# STM32MP25XXAK_I_Os.net
KiCad netlist of a schematic drawn in Altium Designer
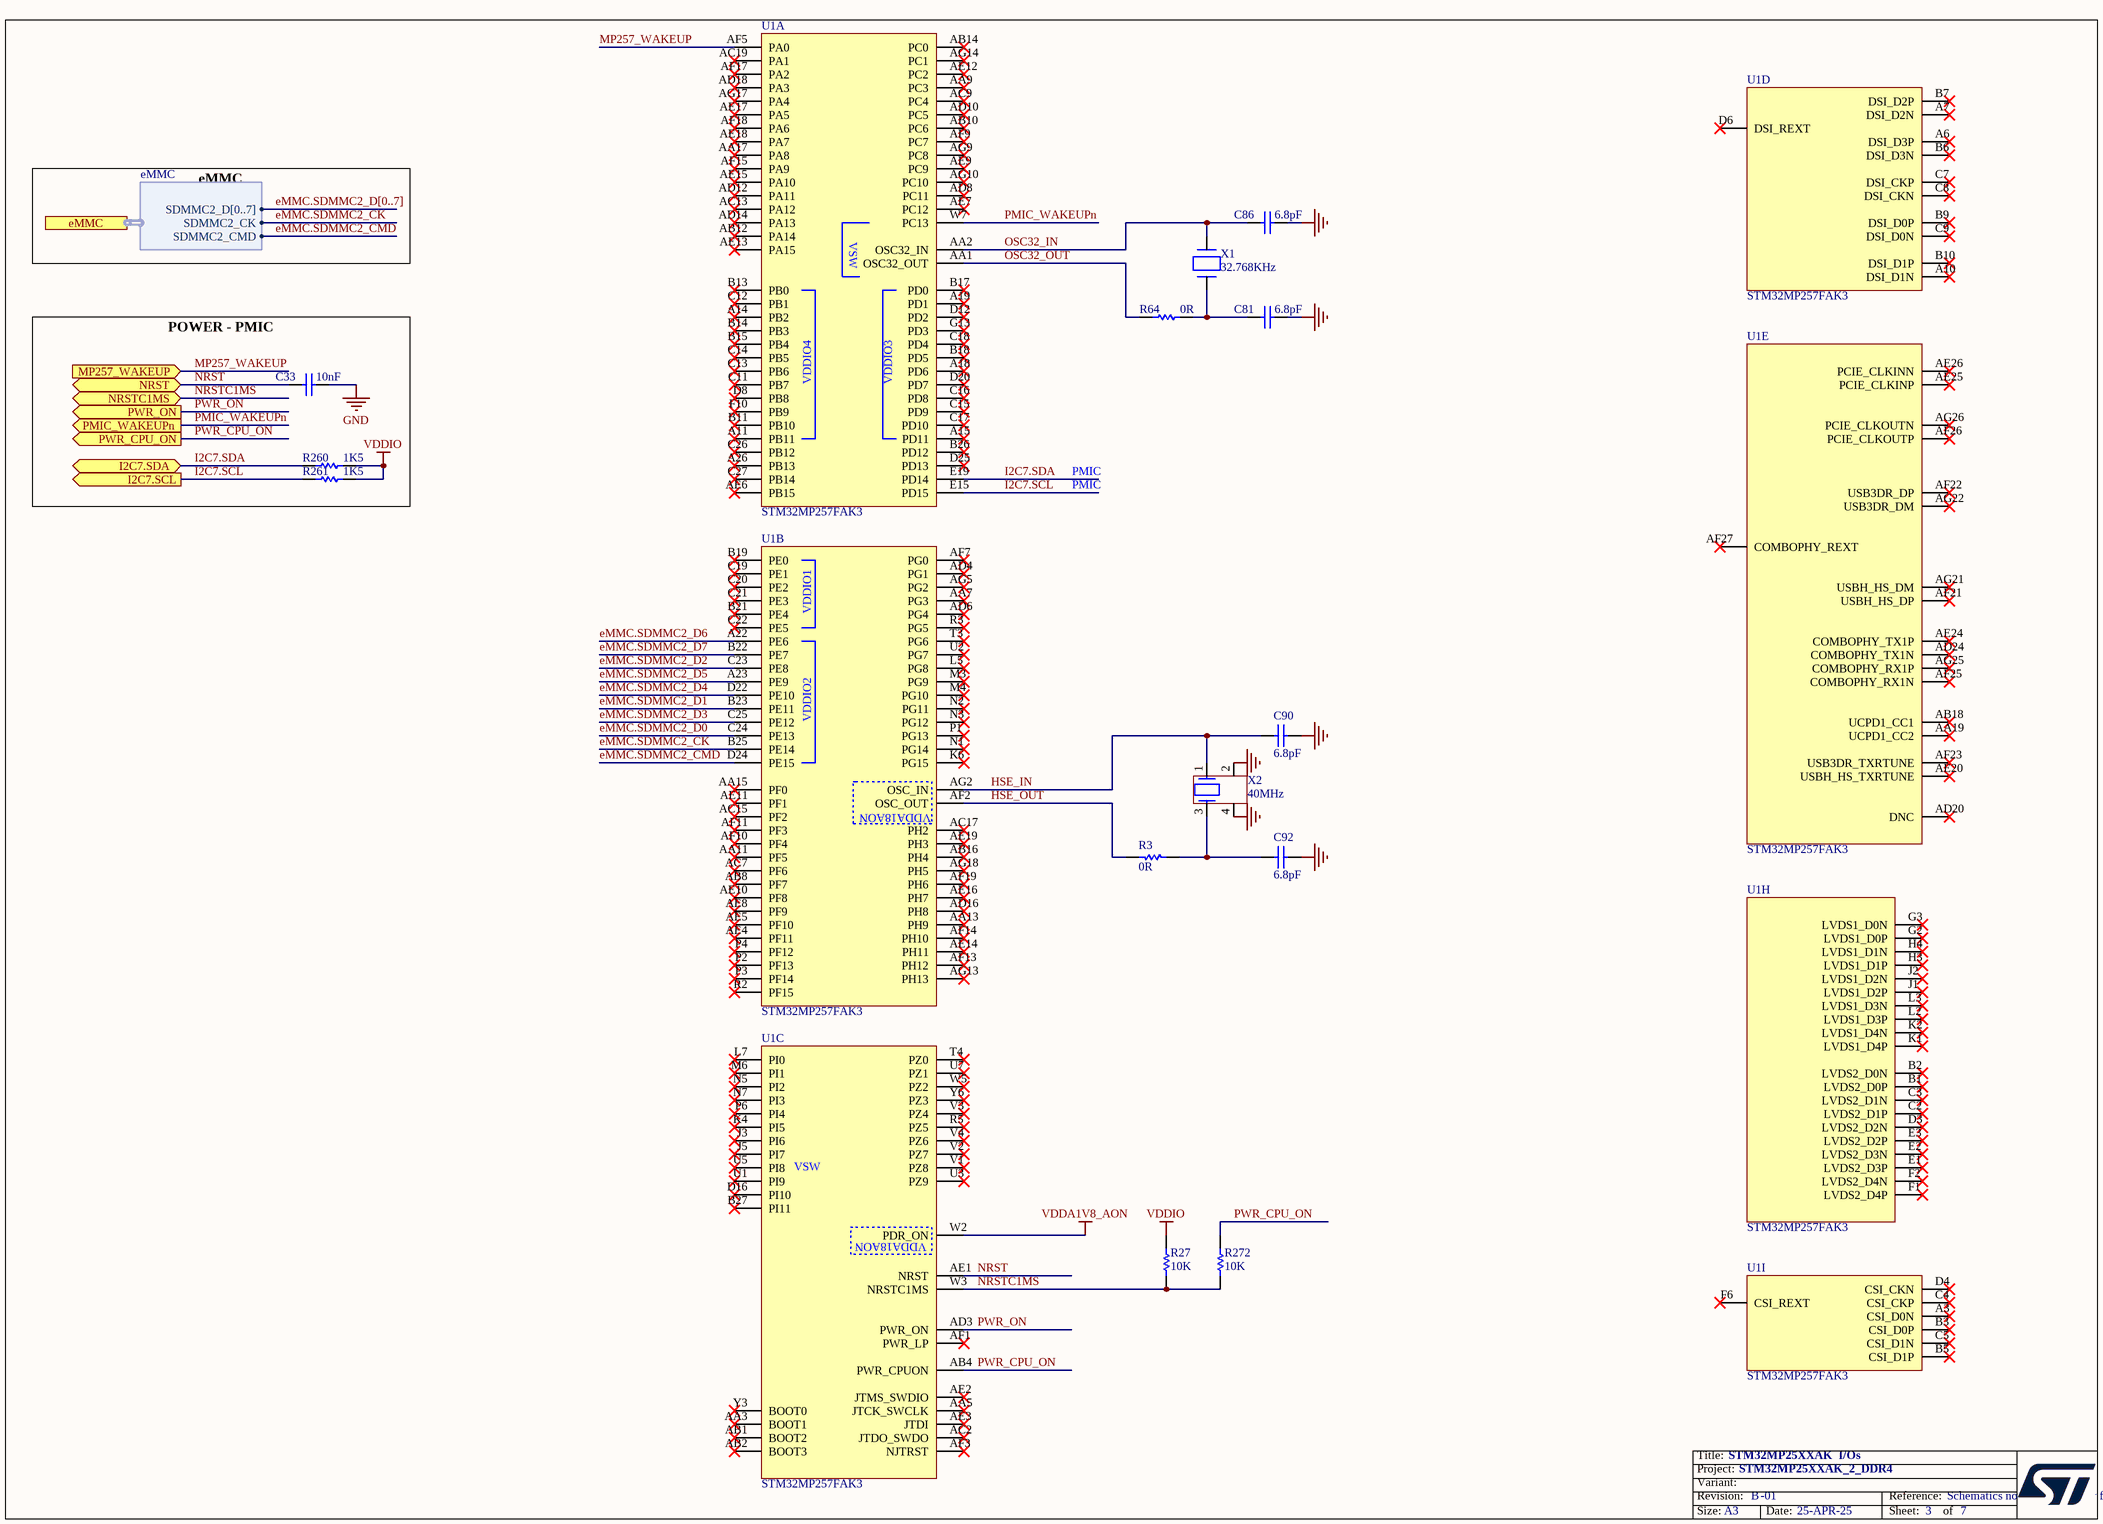
[diagram p0: STM32MP25XXAK I_Os.SchDoc]

(export (version "E")
  (design (tool "Eeschema 10.0.6"))
  (components
    (comp (ref "C33")
      (value "10nF")
      (footprint "C0402")
      (description "Capacitor, MLCC, 10nF, 16V, X7R, 10%, 0402, T=0.5mm")
      (fields
        (field (name "INTERNAL_PART_NUMBER") "MCD-00011")
        (field (name "MANUFACTURER_PART_NUMBER") "CC0402KRX7R7BB103")
        (field (name "PROVIDED_BY") "SUBCO")
      )
      (libsource (lib "MCD_PARTS_database") (part "Capacitor"))
    )
    (comp (ref "C81")
      (value "6.8pF")
      (footprint "C0402")
      (description "Capacitor, MLCC, 6.8pF, 50V, NPO, +-0.25pF, 0402, T=0.5mm")
      (fields
        (field (name "INTERNAL_PART_NUMBER") "MCD-00674")
        (field (name "MANUFACTURER_PART_NUMBER") "CC0402CRNPO9BN6R8")
        (field (name "PROVIDED_BY") "SUBCO")
      )
      (libsource (lib "MCD_PARTS_database") (part "Capacitor"))
    )
    (comp (ref "C86")
      (value "6.8pF")
      (footprint "C0402")
      (description "Capacitor, MLCC, 6.8pF, 50V, NPO, +-0.25pF, 0402, T=0.5mm")
      (fields
        (field (name "INTERNAL_PART_NUMBER") "MCD-00674")
        (field (name "MANUFACTURER_PART_NUMBER") "CC0402CRNPO9BN6R8")
        (field (name "PROVIDED_BY") "SUBCO")
      )
      (libsource (lib "MCD_PARTS_database") (part "Capacitor"))
    )
    (comp (ref "C90")
      (value "6.8pF")
      (footprint "C0402")
      (description "Capacitor, MLCC, 6.8pF, 50V, NPO, +-0.25pF, 0402, T=0.5mm")
      (fields
        (field (name "INTERNAL_PART_NUMBER") "MCD-00674")
        (field (name "MANUFACTURER_PART_NUMBER") "CC0402CRNPO9BN6R8")
        (field (name "PROVIDED_BY") "SUBCO")
      )
      (libsource (lib "MCD_PARTS_database") (part "Capacitor"))
    )
    (comp (ref "C92")
      (value "6.8pF")
      (footprint "C0402")
      (description "Capacitor, MLCC, 6.8pF, 50V, NPO, +-0.25pF, 0402, T=0.5mm")
      (fields
        (field (name "INTERNAL_PART_NUMBER") "MCD-00674")
        (field (name "MANUFACTURER_PART_NUMBER") "CC0402CRNPO9BN6R8")
        (field (name "PROVIDED_BY") "SUBCO")
      )
      (libsource (lib "MCD_PARTS_database") (part "Capacitor"))
    )
    (comp (ref "R3")
      (value "0R")
      (footprint "R0402")
      (description "Resistor,0R,0402,5%,1/16W")
      (fields
        (field (name "INTERNAL_PART_NUMBER") "MCD-00052")
        (field (name "MANUFACTURER_PART_NUMBER") "RC0402JR-070RL")
        (field (name "PROVIDED_BY") "SUBCO")
      )
      (libsource (lib "MCD_PARTS_database") (part "Resistor"))
    )
    (comp (ref "R27")
      (value "10K")
      (footprint "R0402")
      (description "Resistor,10K,0402,1%,1/16W")
      (fields (field (name "INTERNAL_PART_NUMBER") "MCD-00053") (field (name "BMS_PART_NUMBER") "9131590"))
      (libsource (lib "MCD_PARTS_database") (part "Resistor"))
    )
    (comp (ref "R64")
      (value "0R")
      (footprint "R0402")
      (description "Resistor,0R,0402,5%,1/16W")
      (fields
        (field (name "INTERNAL_PART_NUMBER") "MCD-00052")
        (field (name "MANUFACTURER_PART_NUMBER") "RC0402JR-070RL")
        (field (name "PROVIDED_BY") "SUBCO")
      )
      (libsource (lib "MCD_PARTS_database") (part "Resistor"))
    )
    (comp (ref "R260")
      (value "1K5")
      (footprint "R0402")
      (description "Resistor,1K5,0402,1%,1/16W")
      (fields (field (name "INTERNAL_PART_NUMBER") "MCD-00068") (field (name "MANUFACTURER") "YAGEO"))
      (libsource (lib "MCD_PARTS_database") (part "Resistor"))
    )
    (comp (ref "R261")
      (value "1K5")
      (footprint "R0402")
      (description "Resistor,1K5,0402,1%,1/16W")
      (fields (field (name "INTERNAL_PART_NUMBER") "MCD-00068") (field (name "MANUFACTURER") "YAGEO"))
      (libsource (lib "MCD_PARTS_database") (part "Resistor"))
    )
    (comp (ref "R272")
      (value "10K")
      (footprint "R0402")
      (description "Resistor,10K,0402,1%,1/16W")
      (fields (field (name "INTERNAL_PART_NUMBER") "MCD-00053") (field (name "BMS_PART_NUMBER") "9131590"))
      (libsource (lib "MCD_PARTS_database") (part "Resistor"))
    )
    (comp (ref "U1")
      (value "STM32MP257FAK3")
      (footprint "ICC_TFBGA424_14X14_P050_H1P20_CODE-B0A2")
      (description "MPU , 2xCortex-A35@1.5GHz, Cortex-M33@400MHz, TFBGA 14x14, pitch 0.5, 648KB SRAM, With Crypto")
      (fields
        (field (name "INTERNAL_PART_NUMBER") "MCD-03375")
        (field (name "MANUFACTURER") "STMICROELECTRONICS")
      )
      (libsource (lib "MCD_PARTS_database") (part "STM32MP257FAK3"))
    )
    (comp (ref "X1")
      (value "32.768KHz")
      (footprint "CRY_NX2012SA_2P")
      (description "Crystal, 32.768kHz, 6pF, +/-20ppm, 80K, 2.05x1.2mm")
      (fields (field (name "INTERNAL_PART_NUMBER") "MCD-01479") (field (name "BMS_PART_NUMBER") "9157049"))
      (libsource (lib "MCD_PARTS_database") (part "XTAL_2_PINS"))
    )
    (comp (ref "X2")
      (value "40MHz")
      (footprint "CRY_NX1612SA_4P")
      (description "Crystal, 40MHz, 6pF, +/-20ppm, 80R, 1.6x1.2mm")
      (fields (field (name "INTERNAL_PART_NUMBER") "MCD-02344") (field (name "MANUFACTURER") "NDK"))
      (libsource (lib "MCD_PARTS_database") (part "XTAL_4_PINS"))
    )
  )
  (nets
    (net (code "2") (name "/HSE_IN") (class "Default")
      (node (ref "C90") (pin "2") (pinfunction "2_2") (pintype "passive"))
      (node (ref "U1") (pin "AG2") (pinfunction "OSC_IN_AG2") (pintype "passive"))
      (node (ref "X2") (pin "1") (pinfunction "1_1") (pintype "passive"))
    )
    (net (code "3") (name "/HSE_OUT") (class "Default")
      (node (ref "R3") (pin "2") (pinfunction "2_2") (pintype "passive"))
      (node (ref "U1") (pin "AF2") (pinfunction "OSC_OUT_AF2") (pintype "passive"))
    )
    (net (code "4") (name "/I2C7.SCL") (class "Default")
      (node (ref "R261") (pin "1") (pinfunction "1_1") (pintype "passive"))
      (node (ref "U1") (pin "E15") (pinfunction "PD15_E15") (pintype "passive"))
    )
    (net (code "5") (name "/I2C7.SDA") (class "Default")
      (node (ref "R260") (pin "1") (pinfunction "1_1") (pintype "passive"))
      (node (ref "U1") (pin "E19") (pinfunction "PD14_E19") (pintype "passive"))
    )
    (net (code "6") (name "/MP257_WAKEUP") (class "Default")
      (node (ref "U1") (pin "AF5") (pinfunction "PA0_AF5") (pintype "passive"))
    )
    (net (code "7") (name "/NRST") (class "Default")
      (node (ref "C33") (pin "2") (pinfunction "2_2") (pintype "passive"))
      (node (ref "U1") (pin "AE1") (pinfunction "NRST_AE1") (pintype "passive"))
    )
    (net (code "8") (name "/NRSTC1MS") (class "Default")
      (node (ref "R27") (pin "1") (pinfunction "1_1") (pintype "passive"))
      (node (ref "R272") (pin "1") (pinfunction "1_1") (pintype "passive"))
      (node (ref "U1") (pin "W3") (pinfunction "NRSTC1MS_W3") (pintype "passive"))
    )
    (net (code "9") (name "/OSC32_IN") (class "Default")
      (node (ref "C86") (pin "1") (pinfunction "1_1") (pintype "passive"))
      (node (ref "U1") (pin "AA2") (pinfunction "OSC32_IN_AA2") (pintype "passive"))
      (node (ref "X1") (pin "2") (pinfunction "X2_2") (pintype "passive"))
    )
    (net (code "10") (name "/OSC32_OUT") (class "Default")
      (node (ref "R64") (pin "1") (pinfunction "1_1") (pintype "passive"))
      (node (ref "U1") (pin "AA1") (pinfunction "OSC32_OUT_AA1") (pintype "passive"))
    )
    (net (code "11") (name "/PMIC_WAKEUPn") (class "Default")
      (node (ref "U1") (pin "W7") (pinfunction "PC13_W7") (pintype "passive"))
    )
    (net (code "12") (name "/PWR_CPU_ON") (class "Default")
      (node (ref "R272") (pin "2") (pinfunction "2_2") (pintype "passive"))
      (node (ref "U1") (pin "AB4") (pinfunction "PWR_CPUON_AB4") (pintype "passive"))
    )
    (net (code "13") (name "/PWR_ON") (class "Default")
      (node (ref "U1") (pin "AD3") (pinfunction "PWR_ON_AD3") (pintype "passive"))
    )
    (net (code "14") (name "/eMMC.SDMMC2_CK") (class "Default")
      (node (ref "U1") (pin "B25") (pinfunction "PE14_B25") (pintype "passive"))
    )
    (net (code "15") (name "/eMMC.SDMMC2_CMD") (class "Default")
      (node (ref "U1") (pin "D24") (pinfunction "PE15_D24") (pintype "passive"))
    )
    (net (code "16") (name "/eMMC.SDMMC2_D0") (class "Default")
      (node (ref "U1") (pin "C24") (pinfunction "PE13_C24") (pintype "passive"))
    )
    (net (code "17") (name "/eMMC.SDMMC2_D1") (class "Default")
      (node (ref "U1") (pin "B23") (pinfunction "PE11_B23") (pintype "passive"))
    )
    (net (code "18") (name "/eMMC.SDMMC2_D2") (class "Default")
      (node (ref "U1") (pin "C23") (pinfunction "PE8_C23") (pintype "passive"))
    )
    (net (code "19") (name "/eMMC.SDMMC2_D3") (class "Default")
      (node (ref "U1") (pin "C25") (pinfunction "PE12_C25") (pintype "passive"))
    )
    (net (code "20") (name "/eMMC.SDMMC2_D4") (class "Default")
      (node (ref "U1") (pin "D22") (pinfunction "PE10_D22") (pintype "passive"))
    )
    (net (code "21") (name "/eMMC.SDMMC2_D5") (class "Default")
      (node (ref "U1") (pin "A23") (pinfunction "PE9_A23") (pintype "passive"))
    )
    (net (code "22") (name "/eMMC.SDMMC2_D6") (class "Default")
      (node (ref "U1") (pin "A22") (pinfunction "PE6_A22") (pintype "passive"))
    )
    (net (code "23") (name "/eMMC.SDMMC2_D7") (class "Default")
      (node (ref "U1") (pin "B22") (pinfunction "PE7_B22") (pintype "passive"))
    )
    (net (code "26") (name "GND") (class "Default")
      (node (ref "C33") (pin "1") (pinfunction "1_1") (pintype "passive"))
      (node (ref "C81") (pin "2") (pinfunction "2_2") (pintype "passive"))
      (node (ref "C86") (pin "2") (pinfunction "2_2") (pintype "passive"))
      (node (ref "C90") (pin "1") (pinfunction "1_1") (pintype "passive"))
      (node (ref "C92") (pin "2") (pinfunction "2_2") (pintype "passive"))
      (node (ref "X2") (pin "2") (pinfunction "2_2") (pintype "passive"))
      (node (ref "X2") (pin "4") (pinfunction "4_4") (pintype "passive"))
    )
    (net (code "27") (name "Net-(C92-Pad1)") (class "Default")
      (node (ref "C92") (pin "1") (pinfunction "1_1") (pintype "passive"))
      (node (ref "R3") (pin "1") (pinfunction "1_1") (pintype "passive"))
      (node (ref "X2") (pin "3") (pinfunction "3_3") (pintype "passive"))
    )
    (net (code "28") (name "Net-(X1-X1)") (class "Default")
      (node (ref "C81") (pin "1") (pinfunction "1_1") (pintype "passive"))
      (node (ref "R64") (pin "2") (pinfunction "2_2") (pintype "passive"))
      (node (ref "X1") (pin "1") (pinfunction "X1_1") (pintype "passive"))
    )
    (net (code "29") (name "VDDA1V8_AON") (class "Default")
      (node (ref "U1") (pin "W2") (pinfunction "PDR_ON_W2") (pintype "passive"))
    )
    (net (code "30") (name "VDDIO") (class "Default")
      (node (ref "R260") (pin "2") (pinfunction "2_2") (pintype "passive"))
      (node (ref "R261") (pin "2") (pinfunction "2_2") (pintype "passive"))
      (node (ref "R27") (pin "2") (pinfunction "2_2") (pintype "passive"))
    )
    (net (code "31") (name "unconnected-(U1A-PA1-PadAC19)") (class "Default")
      (node (ref "U1") (pin "AC19") (pinfunction "PA1_AC19") (pintype "passive+no_connect"))
    )
    (net (code "32") (name "unconnected-(U1A-PA2-PadAF17)") (class "Default")
      (node (ref "U1") (pin "AF17") (pinfunction "PA2_AF17") (pintype "passive+no_connect"))
    )
    (net (code "33") (name "unconnected-(U1A-PA3-PadAD18)") (class "Default")
      (node (ref "U1") (pin "AD18") (pinfunction "PA3_AD18") (pintype "passive+no_connect"))
    )
    (net (code "34") (name "unconnected-(U1A-PA4-PadAG17)") (class "Default")
      (node (ref "U1") (pin "AG17") (pinfunction "PA4_AG17") (pintype "passive+no_connect"))
    )
    (net (code "35") (name "unconnected-(U1A-PA5-PadAE17)") (class "Default")
      (node (ref "U1") (pin "AE17") (pinfunction "PA5_AE17") (pintype "passive+no_connect"))
    )
    (net (code "36") (name "unconnected-(U1A-PA6-PadAF18)") (class "Default")
      (node (ref "U1") (pin "AF18") (pinfunction "PA6_AF18") (pintype "passive+no_connect"))
    )
    (net (code "37") (name "unconnected-(U1A-PA7-PadAE18)") (class "Default")
      (node (ref "U1") (pin "AE18") (pinfunction "PA7_AE18") (pintype "passive+no_connect"))
    )
    (net (code "38") (name "unconnected-(U1A-PA8-PadAA17)") (class "Default")
      (node (ref "U1") (pin "AA17") (pinfunction "PA8_AA17") (pintype "passive+no_connect"))
    )
    (net (code "39") (name "unconnected-(U1A-PA9-PadAF15)") (class "Default")
      (node (ref "U1") (pin "AF15") (pinfunction "PA9_AF15") (pintype "passive+no_connect"))
    )
    (net (code "40") (name "unconnected-(U1A-PA10-PadAE15)") (class "Default")
      (node (ref "U1") (pin "AE15") (pinfunction "PA10_AE15") (pintype "passive+no_connect"))
    )
    (net (code "41") (name "unconnected-(U1A-PA11-PadAD12)") (class "Default")
      (node (ref "U1") (pin "AD12") (pinfunction "PA11_AD12") (pintype "passive+no_connect"))
    )
    (net (code "42") (name "unconnected-(U1A-PA12-PadAC13)") (class "Default")
      (node (ref "U1") (pin "AC13") (pinfunction "PA12_AC13") (pintype "passive+no_connect"))
    )
    (net (code "43") (name "unconnected-(U1A-PA13-PadAD14)") (class "Default")
      (node (ref "U1") (pin "AD14") (pinfunction "PA13_AD14") (pintype "passive+no_connect"))
    )
    (net (code "44") (name "unconnected-(U1A-PA14-PadAB12)") (class "Default")
      (node (ref "U1") (pin "AB12") (pinfunction "PA14_AB12") (pintype "passive+no_connect"))
    )
    (net (code "45") (name "unconnected-(U1A-PA15-PadAE13)") (class "Default")
      (node (ref "U1") (pin "AE13") (pinfunction "PA15_AE13") (pintype "passive+no_connect"))
    )
    (net (code "46") (name "unconnected-(U1A-PB0-PadB13)") (class "Default")
      (node (ref "U1") (pin "B13") (pinfunction "PB0_B13") (pintype "passive+no_connect"))
    )
    (net (code "47") (name "unconnected-(U1A-PB1-PadC12)") (class "Default")
      (node (ref "U1") (pin "C12") (pinfunction "PB1_C12") (pintype "passive+no_connect"))
    )
    (net (code "48") (name "unconnected-(U1A-PB2-PadA14)") (class "Default")
      (node (ref "U1") (pin "A14") (pinfunction "PB2_A14") (pintype "passive+no_connect"))
    )
    (net (code "49") (name "unconnected-(U1A-PB3-PadB14)") (class "Default")
      (node (ref "U1") (pin "B14") (pinfunction "PB3_B14") (pintype "passive+no_connect"))
    )
    (net (code "50") (name "unconnected-(U1A-PB4-PadB15)") (class "Default")
      (node (ref "U1") (pin "B15") (pinfunction "PB4_B15") (pintype "passive+no_connect"))
    )
    (net (code "51") (name "unconnected-(U1A-PB5-PadC14)") (class "Default")
      (node (ref "U1") (pin "C14") (pinfunction "PB5_C14") (pintype "passive+no_connect"))
    )
    (net (code "52") (name "unconnected-(U1A-PB6-PadC13)") (class "Default")
      (node (ref "U1") (pin "C13") (pinfunction "PB6_C13") (pintype "passive+no_connect"))
    )
    (net (code "53") (name "unconnected-(U1A-PB7-PadC11)") (class "Default")
      (node (ref "U1") (pin "C11") (pinfunction "PB7_C11") (pintype "passive+no_connect"))
    )
    (net (code "54") (name "unconnected-(U1A-PB8-PadD8)") (class "Default")
      (node (ref "U1") (pin "D8") (pinfunction "PB8_D8") (pintype "passive+no_connect"))
    )
    (net (code "55") (name "unconnected-(U1A-PB9-PadF10)") (class "Default")
      (node (ref "U1") (pin "F10") (pinfunction "PB9_F10") (pintype "passive+no_connect"))
    )
    (net (code "56") (name "unconnected-(U1A-PB10-PadB11)") (class "Default")
      (node (ref "U1") (pin "B11") (pinfunction "PB10_B11") (pintype "passive+no_connect"))
    )
    (net (code "57") (name "unconnected-(U1A-PB11-PadA11)") (class "Default")
      (node (ref "U1") (pin "A11") (pinfunction "PB11_A11") (pintype "passive+no_connect"))
    )
    (net (code "58") (name "unconnected-(U1A-PB12-PadC26)") (class "Default")
      (node (ref "U1") (pin "C26") (pinfunction "PB12_C26") (pintype "passive+no_connect"))
    )
    (net (code "59") (name "unconnected-(U1A-PB13-PadA26)") (class "Default")
      (node (ref "U1") (pin "A26") (pinfunction "PB13_A26") (pintype "passive+no_connect"))
    )
    (net (code "60") (name "unconnected-(U1A-PB14-PadC27)") (class "Default")
      (node (ref "U1") (pin "C27") (pinfunction "PB14_C27") (pintype "passive+no_connect"))
    )
    (net (code "61") (name "unconnected-(U1A-PB15-PadAE6)") (class "Default")
      (node (ref "U1") (pin "AE6") (pinfunction "PB15_AE6") (pintype "passive+no_connect"))
    )
    (net (code "62") (name "unconnected-(U1A-PC0-PadAB14)") (class "Default")
      (node (ref "U1") (pin "AB14") (pinfunction "PC0_AB14") (pintype "passive+no_connect"))
    )
    (net (code "63") (name "unconnected-(U1A-PC1-PadAG14)") (class "Default")
      (node (ref "U1") (pin "AG14") (pinfunction "PC1_AG14") (pintype "passive+no_connect"))
    )
    (net (code "64") (name "unconnected-(U1A-PC2-PadAE12)") (class "Default")
      (node (ref "U1") (pin "AE12") (pinfunction "PC2_AE12") (pintype "passive+no_connect"))
    )
    (net (code "65") (name "unconnected-(U1A-PC3-PadAA9)") (class "Default")
      (node (ref "U1") (pin "AA9") (pinfunction "PC3_AA9") (pintype "passive+no_connect"))
    )
    (net (code "66") (name "unconnected-(U1A-PC4-PadAC9)") (class "Default")
      (node (ref "U1") (pin "AC9") (pinfunction "PC4_AC9") (pintype "passive+no_connect"))
    )
    (net (code "67") (name "unconnected-(U1A-PC5-PadAD10)") (class "Default")
      (node (ref "U1") (pin "AD10") (pinfunction "PC5_AD10") (pintype "passive+no_connect"))
    )
    (net (code "68") (name "unconnected-(U1A-PC6-PadAB10)") (class "Default")
      (node (ref "U1") (pin "AB10") (pinfunction "PC6_AB10") (pintype "passive+no_connect"))
    )
    (net (code "69") (name "unconnected-(U1A-PC7-PadAF9)") (class "Default")
      (node (ref "U1") (pin "AF9") (pinfunction "PC7_AF9") (pintype "passive+no_connect"))
    )
    (net (code "70") (name "unconnected-(U1A-PC8-PadAG9)") (class "Default")
      (node (ref "U1") (pin "AG9") (pinfunction "PC8_AG9") (pintype "passive+no_connect"))
    )
    (net (code "71") (name "unconnected-(U1A-PC9-PadAE9)") (class "Default")
      (node (ref "U1") (pin "AE9") (pinfunction "PC9_AE9") (pintype "passive+no_connect"))
    )
    (net (code "72") (name "unconnected-(U1A-PC10-PadAG10)") (class "Default")
      (node (ref "U1") (pin "AG10") (pinfunction "PC10_AG10") (pintype "passive+no_connect"))
    )
    (net (code "73") (name "unconnected-(U1A-PC11-PadAD8)") (class "Default")
      (node (ref "U1") (pin "AD8") (pinfunction "PC11_AD8") (pintype "passive+no_connect"))
    )
    (net (code "74") (name "unconnected-(U1A-PC12-PadAE7)") (class "Default")
      (node (ref "U1") (pin "AE7") (pinfunction "PC12_AE7") (pintype "passive+no_connect"))
    )
    (net (code "75") (name "unconnected-(U1A-PD0-PadB17)") (class "Default")
      (node (ref "U1") (pin "B17") (pinfunction "PD0_B17") (pintype "passive+no_connect"))
    )
    (net (code "76") (name "unconnected-(U1A-PD1-PadA19)") (class "Default")
      (node (ref "U1") (pin "A19") (pinfunction "PD1_A19") (pintype "passive+no_connect"))
    )
    (net (code "77") (name "unconnected-(U1A-PD2-PadD12)") (class "Default")
      (node (ref "U1") (pin "D12") (pinfunction "PD2_D12") (pintype "passive+no_connect"))
    )
    (net (code "78") (name "unconnected-(U1A-PD3-PadG13)") (class "Default")
      (node (ref "U1") (pin "G13") (pinfunction "PD3_G13") (pintype "passive+no_connect"))
    )
    (net (code "79") (name "unconnected-(U1A-PD4-PadC18)") (class "Default")
      (node (ref "U1") (pin "C18") (pinfunction "PD4_C18") (pintype "passive+no_connect"))
    )
    (net (code "80") (name "unconnected-(U1A-PD5-PadB18)") (class "Default")
      (node (ref "U1") (pin "B18") (pinfunction "PD5_B18") (pintype "passive+no_connect"))
    )
    (net (code "81") (name "unconnected-(U1A-PD6-PadA18)") (class "Default")
      (node (ref "U1") (pin "A18") (pinfunction "PD6_A18") (pintype "passive+no_connect"))
    )
    (net (code "82") (name "unconnected-(U1A-PD7-PadD20)") (class "Default")
      (node (ref "U1") (pin "D20") (pinfunction "PD7_D20") (pintype "passive+no_connect"))
    )
    (net (code "83") (name "unconnected-(U1A-PD8-PadC16)") (class "Default")
      (node (ref "U1") (pin "C16") (pinfunction "PD8_C16") (pintype "passive+no_connect"))
    )
    (net (code "84") (name "unconnected-(U1A-PD9-PadC15)") (class "Default")
      (node (ref "U1") (pin "C15") (pinfunction "PD9_C15") (pintype "passive+no_connect"))
    )
    (net (code "85") (name "unconnected-(U1A-PD10-PadC17)") (class "Default")
      (node (ref "U1") (pin "C17") (pinfunction "PD10_C17") (pintype "passive+no_connect"))
    )
    (net (code "86") (name "unconnected-(U1A-PD11-PadA15)") (class "Default")
      (node (ref "U1") (pin "A15") (pinfunction "PD11_A15") (pintype "passive+no_connect"))
    )
    (net (code "87") (name "unconnected-(U1A-PD12-PadB26)") (class "Default")
      (node (ref "U1") (pin "B26") (pinfunction "PD12_B26") (pintype "passive+no_connect"))
    )
    (net (code "88") (name "unconnected-(U1A-PD13-PadD25)") (class "Default")
      (node (ref "U1") (pin "D25") (pinfunction "PD13_D25") (pintype "passive+no_connect"))
    )
    (net (code "89") (name "unconnected-(U1B-PE0-PadB19)") (class "Default")
      (node (ref "U1") (pin "B19") (pinfunction "PE0_B19") (pintype "passive+no_connect"))
    )
    (net (code "90") (name "unconnected-(U1B-PE1-PadC19)") (class "Default")
      (node (ref "U1") (pin "C19") (pinfunction "PE1_C19") (pintype "passive+no_connect"))
    )
    (net (code "91") (name "unconnected-(U1B-PE2-PadC20)") (class "Default")
      (node (ref "U1") (pin "C20") (pinfunction "PE2_C20") (pintype "passive+no_connect"))
    )
    (net (code "92") (name "unconnected-(U1B-PE3-PadC21)") (class "Default")
      (node (ref "U1") (pin "C21") (pinfunction "PE3_C21") (pintype "passive+no_connect"))
    )
    (net (code "93") (name "unconnected-(U1B-PE4-PadB21)") (class "Default")
      (node (ref "U1") (pin "B21") (pinfunction "PE4_B21") (pintype "passive+no_connect"))
    )
    (net (code "94") (name "unconnected-(U1B-PE5-PadC22)") (class "Default")
      (node (ref "U1") (pin "C22") (pinfunction "PE5_C22") (pintype "passive+no_connect"))
    )
    (net (code "95") (name "unconnected-(U1B-PF0-PadAA15)") (class "Default")
      (node (ref "U1") (pin "AA15") (pinfunction "PF0_AA15") (pintype "passive+no_connect"))
    )
    (net (code "96") (name "unconnected-(U1B-PF1-PadAE11)") (class "Default")
      (node (ref "U1") (pin "AE11") (pinfunction "PF1_AE11") (pintype "passive+no_connect"))
    )
    (net (code "97") (name "unconnected-(U1B-PF2-PadAC15)") (class "Default")
      (node (ref "U1") (pin "AC15") (pinfunction "PF2_AC15") (pintype "passive+no_connect"))
    )
    (net (code "98") (name "unconnected-(U1B-PF3-PadAF11)") (class "Default")
      (node (ref "U1") (pin "AF11") (pinfunction "PF3_AF11") (pintype "passive+no_connect"))
    )
    (net (code "99") (name "unconnected-(U1B-PF4-PadAF10)") (class "Default")
      (node (ref "U1") (pin "AF10") (pinfunction "PF4_AF10") (pintype "passive+no_connect"))
    )
    (net (code "100") (name "unconnected-(U1B-PF5-PadAA11)") (class "Default")
      (node (ref "U1") (pin "AA11") (pinfunction "PF5_AA11") (pintype "passive+no_connect"))
    )
    (net (code "101") (name "unconnected-(U1B-PF6-PadAC7)") (class "Default")
      (node (ref "U1") (pin "AC7") (pinfunction "PF6_AC7") (pintype "passive+no_connect"))
    )
    (net (code "102") (name "unconnected-(U1B-PF7-PadAB8)") (class "Default")
      (node (ref "U1") (pin "AB8") (pinfunction "PF7_AB8") (pintype "passive+no_connect"))
    )
    (net (code "103") (name "unconnected-(U1B-PF8-PadAE10)") (class "Default")
      (node (ref "U1") (pin "AE10") (pinfunction "PF8_AE10") (pintype "passive+no_connect"))
    )
    (net (code "104") (name "unconnected-(U1B-PF9-PadAE8)") (class "Default")
      (node (ref "U1") (pin "AE8") (pinfunction "PF9_AE8") (pintype "passive+no_connect"))
    )
    (net (code "105") (name "unconnected-(U1B-PF10-PadAE5)") (class "Default")
      (node (ref "U1") (pin "AE5") (pinfunction "PF10_AE5") (pintype "passive+no_connect"))
    )
    (net (code "106") (name "unconnected-(U1B-PF11-PadAE4)") (class "Default")
      (node (ref "U1") (pin "AE4") (pinfunction "PF11_AE4") (pintype "passive+no_connect"))
    )
    (net (code "107") (name "unconnected-(U1B-PF12-PadP4)") (class "Default")
      (node (ref "U1") (pin "P4") (pinfunction "PF12_P4") (pintype "passive+no_connect"))
    )
    (net (code "108") (name "unconnected-(U1B-PF13-PadP2)") (class "Default")
      (node (ref "U1") (pin "P2") (pinfunction "PF13_P2") (pintype "passive+no_connect"))
    )
    (net (code "109") (name "unconnected-(U1B-PF14-PadP3)") (class "Default")
      (node (ref "U1") (pin "P3") (pinfunction "PF14_P3") (pintype "passive+no_connect"))
    )
    (net (code "110") (name "unconnected-(U1B-PF15-PadR2)") (class "Default")
      (node (ref "U1") (pin "R2") (pinfunction "PF15_R2") (pintype "passive+no_connect"))
    )
    (net (code "111") (name "unconnected-(U1B-PG0-PadAF7)") (class "Default")
      (node (ref "U1") (pin "AF7") (pinfunction "PG0_AF7") (pintype "passive+no_connect"))
    )
    (net (code "112") (name "unconnected-(U1B-PG1-PadAD4)") (class "Default")
      (node (ref "U1") (pin "AD4") (pinfunction "PG1_AD4") (pintype "passive+no_connect"))
    )
    (net (code "113") (name "unconnected-(U1B-PG2-PadAG5)") (class "Default")
      (node (ref "U1") (pin "AG5") (pinfunction "PG2_AG5") (pintype "passive+no_connect"))
    )
    (net (code "114") (name "unconnected-(U1B-PG3-PadAA7)") (class "Default")
      (node (ref "U1") (pin "AA7") (pinfunction "PG3_AA7") (pintype "passive+no_connect"))
    )
    (net (code "115") (name "unconnected-(U1B-PG4-PadAD6)") (class "Default")
      (node (ref "U1") (pin "AD6") (pinfunction "PG4_AD6") (pintype "passive+no_connect"))
    )
    (net (code "116") (name "unconnected-(U1B-PG5-PadR3)") (class "Default")
      (node (ref "U1") (pin "R3") (pinfunction "PG5_R3") (pintype "passive+no_connect"))
    )
    (net (code "117") (name "unconnected-(U1B-PG6-PadT3)") (class "Default")
      (node (ref "U1") (pin "T3") (pinfunction "PG6_T3") (pintype "passive+no_connect"))
    )
    (net (code "118") (name "unconnected-(U1B-PG7-PadU2)") (class "Default")
      (node (ref "U1") (pin "U2") (pinfunction "PG7_U2") (pintype "passive+no_connect"))
    )
    (net (code "119") (name "unconnected-(U1B-PG8-PadL5)") (class "Default")
      (node (ref "U1") (pin "L5") (pinfunction "PG8_L5") (pintype "passive+no_connect"))
    )
    (net (code "120") (name "unconnected-(U1B-PG9-PadM3)") (class "Default")
      (node (ref "U1") (pin "M3") (pinfunction "PG9_M3") (pintype "passive+no_connect"))
    )
    (net (code "121") (name "unconnected-(U1B-PG10-PadM4)") (class "Default")
      (node (ref "U1") (pin "M4") (pinfunction "PG10_M4") (pintype "passive+no_connect"))
    )
    (net (code "122") (name "unconnected-(U1B-PG11-PadN2)") (class "Default")
      (node (ref "U1") (pin "N2") (pinfunction "PG11_N2") (pintype "passive+no_connect"))
    )
    (net (code "123") (name "unconnected-(U1B-PG12-PadN3)") (class "Default")
      (node (ref "U1") (pin "N3") (pinfunction "PG12_N3") (pintype "passive+no_connect"))
    )
    (net (code "124") (name "unconnected-(U1B-PG13-PadP1)") (class "Default")
      (node (ref "U1") (pin "P1") (pinfunction "PG13_P1") (pintype "passive+no_connect"))
    )
    (net (code "125") (name "unconnected-(U1B-PG14-PadN1)") (class "Default")
      (node (ref "U1") (pin "N1") (pinfunction "PG14_N1") (pintype "passive+no_connect"))
    )
    (net (code "126") (name "unconnected-(U1B-PG15-PadK6)") (class "Default")
      (node (ref "U1") (pin "K6") (pinfunction "PG15_K6") (pintype "passive+no_connect"))
    )
    (net (code "127") (name "unconnected-(U1B-PH2-PadAC17)") (class "Default")
      (node (ref "U1") (pin "AC17") (pinfunction "PH2_AC17") (pintype "passive+no_connect"))
    )
    (net (code "128") (name "unconnected-(U1B-PH3-PadAE19)") (class "Default")
      (node (ref "U1") (pin "AE19") (pinfunction "PH3_AE19") (pintype "passive+no_connect"))
    )
    (net (code "129") (name "unconnected-(U1B-PH4-PadAB16)") (class "Default")
      (node (ref "U1") (pin "AB16") (pinfunction "PH4_AB16") (pintype "passive+no_connect"))
    )
    (net (code "130") (name "unconnected-(U1B-PH5-PadAG18)") (class "Default")
      (node (ref "U1") (pin "AG18") (pinfunction "PH5_AG18") (pintype "passive+no_connect"))
    )
    (net (code "131") (name "unconnected-(U1B-PH6-PadAF19)") (class "Default")
      (node (ref "U1") (pin "AF19") (pinfunction "PH6_AF19") (pintype "passive+no_connect"))
    )
    (net (code "132") (name "unconnected-(U1B-PH7-PadAE16)") (class "Default")
      (node (ref "U1") (pin "AE16") (pinfunction "PH7_AE16") (pintype "passive+no_connect"))
    )
    (net (code "133") (name "unconnected-(U1B-PH8-PadAD16)") (class "Default")
      (node (ref "U1") (pin "AD16") (pinfunction "PH8_AD16") (pintype "passive+no_connect"))
    )
    (net (code "134") (name "unconnected-(U1B-PH9-PadAA13)") (class "Default")
      (node (ref "U1") (pin "AA13") (pinfunction "PH9_AA13") (pintype "passive+no_connect"))
    )
    (net (code "135") (name "unconnected-(U1B-PH10-PadAF14)") (class "Default")
      (node (ref "U1") (pin "AF14") (pinfunction "PH10_AF14") (pintype "passive+no_connect"))
    )
    (net (code "136") (name "unconnected-(U1B-PH11-PadAE14)") (class "Default")
      (node (ref "U1") (pin "AE14") (pinfunction "PH11_AE14") (pintype "passive+no_connect"))
    )
    (net (code "137") (name "unconnected-(U1B-PH12-PadAF13)") (class "Default")
      (node (ref "U1") (pin "AF13") (pinfunction "PH12_AF13") (pintype "passive+no_connect"))
    )
    (net (code "138") (name "unconnected-(U1B-PH13-PadAG13)") (class "Default")
      (node (ref "U1") (pin "AG13") (pinfunction "PH13_AG13") (pintype "passive+no_connect"))
    )
    (net (code "139") (name "unconnected-(U1C-BOOT0-PadY3)") (class "Default")
      (node (ref "U1") (pin "Y3") (pinfunction "BOOT0_Y3") (pintype "passive+no_connect"))
    )
    (net (code "140") (name "unconnected-(U1C-BOOT1-PadAA3)") (class "Default")
      (node (ref "U1") (pin "AA3") (pinfunction "BOOT1_AA3") (pintype "passive+no_connect"))
    )
    (net (code "141") (name "unconnected-(U1C-BOOT2-PadAB1)") (class "Default")
      (node (ref "U1") (pin "AB1") (pinfunction "BOOT2_AB1") (pintype "passive+no_connect"))
    )
    (net (code "142") (name "unconnected-(U1C-BOOT3-PadAB2)") (class "Default")
      (node (ref "U1") (pin "AB2") (pinfunction "BOOT3_AB2") (pintype "passive+no_connect"))
    )
    (net (code "143") (name "unconnected-(U1C-JTCK_SWCLK-PadAA5)") (class "Default")
      (node (ref "U1") (pin "AA5") (pinfunction "JTCK_SWCLK_AA5") (pintype "passive+no_connect"))
    )
    (net (code "144") (name "unconnected-(U1C-JTDI-PadAE3)") (class "Default")
      (node (ref "U1") (pin "AE3") (pinfunction "JTDI_AE3") (pintype "passive+no_connect"))
    )
    (net (code "145") (name "unconnected-(U1C-JTDO_SWDO-PadAC2)") (class "Default")
      (node (ref "U1") (pin "AC2") (pinfunction "JTDO_SWDO_AC2") (pintype "passive+no_connect"))
    )
    (net (code "146") (name "unconnected-(U1C-JTMS_SWDIO-PadAE2)") (class "Default")
      (node (ref "U1") (pin "AE2") (pinfunction "JTMS_SWDIO_AE2") (pintype "passive+no_connect"))
    )
    (net (code "147") (name "unconnected-(U1C-NJTRST-PadAF3)") (class "Default")
      (node (ref "U1") (pin "AF3") (pinfunction "NJTRST_AF3") (pintype "passive+no_connect"))
    )
    (net (code "148") (name "unconnected-(U1C-PI0-PadL7)") (class "Default")
      (node (ref "U1") (pin "L7") (pinfunction "PI0_L7") (pintype "passive+no_connect"))
    )
    (net (code "149") (name "unconnected-(U1C-PI1-PadM6)") (class "Default")
      (node (ref "U1") (pin "M6") (pinfunction "PI1_M6") (pintype "passive+no_connect"))
    )
    (net (code "150") (name "unconnected-(U1C-PI2-PadN5)") (class "Default")
      (node (ref "U1") (pin "N5") (pinfunction "PI2_N5") (pintype "passive+no_connect"))
    )
    (net (code "151") (name "unconnected-(U1C-PI3-PadN7)") (class "Default")
      (node (ref "U1") (pin "N7") (pinfunction "PI3_N7") (pintype "passive+no_connect"))
    )
    (net (code "152") (name "unconnected-(U1C-PI4-PadP6)") (class "Default")
      (node (ref "U1") (pin "P6") (pinfunction "PI4_P6") (pintype "passive+no_connect"))
    )
    (net (code "153") (name "unconnected-(U1C-PI5-PadK4)") (class "Default")
      (node (ref "U1") (pin "K4") (pinfunction "PI5_K4") (pintype "passive+no_connect"))
    )
    (net (code "154") (name "unconnected-(U1C-PI6-PadJ3)") (class "Default")
      (node (ref "U1") (pin "J3") (pinfunction "PI6_J3") (pintype "passive+no_connect"))
    )
    (net (code "155") (name "unconnected-(U1C-PI7-PadJ5)") (class "Default")
      (node (ref "U1") (pin "J5") (pinfunction "PI7_J5") (pintype "passive+no_connect"))
    )
    (net (code "156") (name "unconnected-(U1C-PI8-PadU5)") (class "Default")
      (node (ref "U1") (pin "U5") (pinfunction "PI8_U5") (pintype "passive+no_connect"))
    )
    (net (code "157") (name "unconnected-(U1C-PI9-PadU1)") (class "Default")
      (node (ref "U1") (pin "U1") (pinfunction "PI9_U1") (pintype "passive+no_connect"))
    )
    (net (code "158") (name "unconnected-(U1C-PI10-PadD16)") (class "Default")
      (node (ref "U1") (pin "D16") (pinfunction "PI10_D16") (pintype "passive+no_connect"))
    )
    (net (code "159") (name "unconnected-(U1C-PI11-PadB27)") (class "Default")
      (node (ref "U1") (pin "B27") (pinfunction "PI11_B27") (pintype "passive+no_connect"))
    )
    (net (code "160") (name "unconnected-(U1C-PWR_LP-PadAF1)") (class "Default")
      (node (ref "U1") (pin "AF1") (pinfunction "PWR_LP_AF1") (pintype "passive+no_connect"))
    )
    (net (code "161") (name "unconnected-(U1C-PZ0-PadT4)") (class "Default")
      (node (ref "U1") (pin "T4") (pinfunction "PZ0_T4") (pintype "passive+no_connect"))
    )
    (net (code "162") (name "unconnected-(U1C-PZ1-PadU7)") (class "Default")
      (node (ref "U1") (pin "U7") (pinfunction "PZ1_U7") (pintype "passive+no_connect"))
    )
    (net (code "163") (name "unconnected-(U1C-PZ2-PadW5)") (class "Default")
      (node (ref "U1") (pin "W5") (pinfunction "PZ2_W5") (pintype "passive+no_connect"))
    )
    (net (code "164") (name "unconnected-(U1C-PZ3-PadY6)") (class "Default")
      (node (ref "U1") (pin "Y6") (pinfunction "PZ3_Y6") (pintype "passive+no_connect"))
    )
    (net (code "165") (name "unconnected-(U1C-PZ4-PadV3)") (class "Default")
      (node (ref "U1") (pin "V3") (pinfunction "PZ4_V3") (pintype "passive+no_connect"))
    )
    (net (code "166") (name "unconnected-(U1C-PZ5-PadR5)") (class "Default")
      (node (ref "U1") (pin "R5") (pinfunction "PZ5_R5") (pintype "passive+no_connect"))
    )
    (net (code "167") (name "unconnected-(U1C-PZ6-PadV4)") (class "Default")
      (node (ref "U1") (pin "V4") (pinfunction "PZ6_V4") (pintype "passive+no_connect"))
    )
    (net (code "168") (name "unconnected-(U1C-PZ7-PadV2)") (class "Default")
      (node (ref "U1") (pin "V2") (pinfunction "PZ7_V2") (pintype "passive+no_connect"))
    )
    (net (code "169") (name "unconnected-(U1C-PZ8-PadV1)") (class "Default")
      (node (ref "U1") (pin "V1") (pinfunction "PZ8_V1") (pintype "passive+no_connect"))
    )
    (net (code "170") (name "unconnected-(U1C-PZ9-PadU3)") (class "Default")
      (node (ref "U1") (pin "U3") (pinfunction "PZ9_U3") (pintype "passive+no_connect"))
    )
    (net (code "171") (name "unconnected-(U1D-DSI_CKN-PadC8)") (class "Default")
      (node (ref "U1") (pin "C8") (pinfunction "DSI_CKN_C8") (pintype "passive+no_connect"))
    )
    (net (code "172") (name "unconnected-(U1D-DSI_CKP-PadC7)") (class "Default")
      (node (ref "U1") (pin "C7") (pinfunction "DSI_CKP_C7") (pintype "passive+no_connect"))
    )
    (net (code "173") (name "unconnected-(U1D-DSI_D0N-PadC9)") (class "Default")
      (node (ref "U1") (pin "C9") (pinfunction "DSI_D0N_C9") (pintype "passive+no_connect"))
    )
    (net (code "174") (name "unconnected-(U1D-DSI_D0P-PadB9)") (class "Default")
      (node (ref "U1") (pin "B9") (pinfunction "DSI_D0P_B9") (pintype "passive+no_connect"))
    )
    (net (code "175") (name "unconnected-(U1D-DSI_D1N-PadA10)") (class "Default")
      (node (ref "U1") (pin "A10") (pinfunction "DSI_D1N_A10") (pintype "passive+no_connect"))
    )
    (net (code "176") (name "unconnected-(U1D-DSI_D1P-PadB10)") (class "Default")
      (node (ref "U1") (pin "B10") (pinfunction "DSI_D1P_B10") (pintype "passive+no_connect"))
    )
    (net (code "177") (name "unconnected-(U1D-DSI_D2N-PadA7)") (class "Default")
      (node (ref "U1") (pin "A7") (pinfunction "DSI_D2N_A7") (pintype "passive+no_connect"))
    )
    (net (code "178") (name "unconnected-(U1D-DSI_D2P-PadB7)") (class "Default")
      (node (ref "U1") (pin "B7") (pinfunction "DSI_D2P_B7") (pintype "passive+no_connect"))
    )
    (net (code "179") (name "unconnected-(U1D-DSI_D3N-PadB6)") (class "Default")
      (node (ref "U1") (pin "B6") (pinfunction "DSI_D3N_B6") (pintype "passive+no_connect"))
    )
    (net (code "180") (name "unconnected-(U1D-DSI_D3P-PadA6)") (class "Default")
      (node (ref "U1") (pin "A6") (pinfunction "DSI_D3P_A6") (pintype "passive+no_connect"))
    )
    (net (code "181") (name "unconnected-(U1D-DSI_REXT-PadD6)") (class "Default")
      (node (ref "U1") (pin "D6") (pinfunction "DSI_REXT_D6") (pintype "passive+no_connect"))
    )
    (net (code "182") (name "unconnected-(U1E-COMBOPHY_REXT-PadAF27)") (class "Default")
      (node (ref "U1") (pin "AF27") (pinfunction "COMBOPHY_REXT_AF27") (pintype "passive+no_connect"))
    )
    (net (code "183") (name "unconnected-(U1E-COMBOPHY_RX1N-PadAF25)") (class "Default")
      (node (ref "U1") (pin "AF25") (pinfunction "COMBOPHY_RX1N_AF25") (pintype "passive+no_connect"))
    )
    (net (code "184") (name "unconnected-(U1E-COMBOPHY_RX1P-PadAG25)") (class "Default")
      (node (ref "U1") (pin "AG25") (pinfunction "COMBOPHY_RX1P_AG25") (pintype "passive+no_connect"))
    )
    (net (code "185") (name "unconnected-(U1E-COMBOPHY_TX1N-PadAD24)") (class "Default")
      (node (ref "U1") (pin "AD24") (pinfunction "COMBOPHY_TX1N_AD24") (pintype "passive+no_connect"))
    )
    (net (code "186") (name "unconnected-(U1E-COMBOPHY_TX1P-PadAE24)") (class "Default")
      (node (ref "U1") (pin "AE24") (pinfunction "COMBOPHY_TX1P_AE24") (pintype "passive+no_connect"))
    )
    (net (code "187") (name "unconnected-(U1E-DNC-PadAD20)") (class "Default")
      (node (ref "U1") (pin "AD20") (pinfunction "DNC_AD20") (pintype "passive+no_connect"))
    )
    (net (code "188") (name "unconnected-(U1E-PCIE_CLKINN-PadAE26)") (class "Default")
      (node (ref "U1") (pin "AE26") (pinfunction "PCIE_CLKINN_AE26") (pintype "passive+no_connect"))
    )
    (net (code "189") (name "unconnected-(U1E-PCIE_CLKINP-PadAE25)") (class "Default")
      (node (ref "U1") (pin "AE25") (pinfunction "PCIE_CLKINP_AE25") (pintype "passive+no_connect"))
    )
    (net (code "190") (name "unconnected-(U1E-PCIE_CLKOUTN-PadAG26)") (class "Default")
      (node (ref "U1") (pin "AG26") (pinfunction "PCIE_CLKOUTN_AG26") (pintype "passive+no_connect"))
    )
    (net (code "191") (name "unconnected-(U1E-PCIE_CLKOUTP-PadAF26)") (class "Default")
      (node (ref "U1") (pin "AF26") (pinfunction "PCIE_CLKOUTP_AF26") (pintype "passive+no_connect"))
    )
    (net (code "192") (name "unconnected-(U1E-UCPD1_CC1-PadAB18)") (class "Default")
      (node (ref "U1") (pin "AB18") (pinfunction "UCPD1_CC1_AB18") (pintype "passive+no_connect"))
    )
    (net (code "193") (name "unconnected-(U1E-UCPD1_CC2-PadAA19)") (class "Default")
      (node (ref "U1") (pin "AA19") (pinfunction "UCPD1_CC2_AA19") (pintype "passive+no_connect"))
    )
    (net (code "194") (name "unconnected-(U1E-USB3DR_DM-PadAG22)") (class "Default")
      (node (ref "U1") (pin "AG22") (pinfunction "USB3DR_DM_AG22") (pintype "passive+no_connect"))
    )
    (net (code "195") (name "unconnected-(U1E-USB3DR_DP-PadAF22)") (class "Default")
      (node (ref "U1") (pin "AF22") (pinfunction "USB3DR_DP_AF22") (pintype "passive+no_connect"))
    )
    (net (code "196") (name "unconnected-(U1E-USB3DR_TXRTUNE-PadAF23)") (class "Default")
      (node (ref "U1") (pin "AF23") (pinfunction "USB3DR_TXRTUNE_AF23") (pintype "passive+no_connect"))
    )
    (net (code "197") (name "unconnected-(U1E-USBH_HS_DM-PadAG21)") (class "Default")
      (node (ref "U1") (pin "AG21") (pinfunction "USBH_HS_DM_AG21") (pintype "passive+no_connect"))
    )
    (net (code "198") (name "unconnected-(U1E-USBH_HS_DP-PadAF21)") (class "Default")
      (node (ref "U1") (pin "AF21") (pinfunction "USBH_HS_DP_AF21") (pintype "passive+no_connect"))
    )
    (net (code "199") (name "unconnected-(U1E-USBH_HS_TXRTUNE-PadAE20)") (class "Default")
      (node (ref "U1") (pin "AE20") (pinfunction "USBH_HS_TXRTUNE_AE20") (pintype "passive+no_connect"))
    )
    (net (code "200") (name "unconnected-(U1H-LVDS1_D0N-PadG3)") (class "Default")
      (node (ref "U1") (pin "G3") (pinfunction "LVDS1_D0N_G3") (pintype "passive+no_connect"))
    )
    (net (code "201") (name "unconnected-(U1H-LVDS1_D0P-PadG2)") (class "Default")
      (node (ref "U1") (pin "G2") (pinfunction "LVDS1_D0P_G2") (pintype "passive+no_connect"))
    )
    (net (code "202") (name "unconnected-(U1H-LVDS1_D1N-PadH4)") (class "Default")
      (node (ref "U1") (pin "H4") (pinfunction "LVDS1_D1N_H4") (pintype "passive+no_connect"))
    )
    (net (code "203") (name "unconnected-(U1H-LVDS1_D1P-PadH3)") (class "Default")
      (node (ref "U1") (pin "H3") (pinfunction "LVDS1_D1P_H3") (pintype "passive+no_connect"))
    )
    (net (code "204") (name "unconnected-(U1H-LVDS1_D2N-PadJ2)") (class "Default")
      (node (ref "U1") (pin "J2") (pinfunction "LVDS1_D2N_J2") (pintype "passive+no_connect"))
    )
    (net (code "205") (name "unconnected-(U1H-LVDS1_D2P-PadJ1)") (class "Default")
      (node (ref "U1") (pin "J1") (pinfunction "LVDS1_D2P_J1") (pintype "passive+no_connect"))
    )
    (net (code "206") (name "unconnected-(U1H-LVDS1_D3N-PadL3)") (class "Default")
      (node (ref "U1") (pin "L3") (pinfunction "LVDS1_D3N_L3") (pintype "passive+no_connect"))
    )
    (net (code "207") (name "unconnected-(U1H-LVDS1_D3P-PadL2)") (class "Default")
      (node (ref "U1") (pin "L2") (pinfunction "LVDS1_D3P_L2") (pintype "passive+no_connect"))
    )
    (net (code "208") (name "unconnected-(U1H-LVDS1_D4N-PadK2)") (class "Default")
      (node (ref "U1") (pin "K2") (pinfunction "LVDS1_D4N_K2") (pintype "passive+no_connect"))
    )
    (net (code "209") (name "unconnected-(U1H-LVDS1_D4P-PadK1)") (class "Default")
      (node (ref "U1") (pin "K1") (pinfunction "LVDS1_D4P_K1") (pintype "passive+no_connect"))
    )
    (net (code "210") (name "unconnected-(U1H-LVDS2_D0N-PadB2)") (class "Default")
      (node (ref "U1") (pin "B2") (pinfunction "LVDS2_D0N_B2") (pintype "passive+no_connect"))
    )
    (net (code "211") (name "unconnected-(U1H-LVDS2_D0P-PadB1)") (class "Default")
      (node (ref "U1") (pin "B1") (pinfunction "LVDS2_D0P_B1") (pintype "passive+no_connect"))
    )
    (net (code "212") (name "unconnected-(U1H-LVDS2_D1N-PadC3)") (class "Default")
      (node (ref "U1") (pin "C3") (pinfunction "LVDS2_D1N_C3") (pintype "passive+no_connect"))
    )
    (net (code "213") (name "unconnected-(U1H-LVDS2_D1P-PadC2)") (class "Default")
      (node (ref "U1") (pin "C2") (pinfunction "LVDS2_D1P_C2") (pintype "passive+no_connect"))
    )
    (net (code "214") (name "unconnected-(U1H-LVDS2_D2N-PadD3)") (class "Default")
      (node (ref "U1") (pin "D3") (pinfunction "LVDS2_D2N_D3") (pintype "passive+no_connect"))
    )
    (net (code "215") (name "unconnected-(U1H-LVDS2_D2P-PadE3)") (class "Default")
      (node (ref "U1") (pin "E3") (pinfunction "LVDS2_D2P_E3") (pintype "passive+no_connect"))
    )
    (net (code "216") (name "unconnected-(U1H-LVDS2_D3N-PadE2)") (class "Default")
      (node (ref "U1") (pin "E2") (pinfunction "LVDS2_D3N_E2") (pintype "passive+no_connect"))
    )
    (net (code "217") (name "unconnected-(U1H-LVDS2_D3P-PadE1)") (class "Default")
      (node (ref "U1") (pin "E1") (pinfunction "LVDS2_D3P_E1") (pintype "passive+no_connect"))
    )
    (net (code "218") (name "unconnected-(U1H-LVDS2_D4N-PadF2)") (class "Default")
      (node (ref "U1") (pin "F2") (pinfunction "LVDS2_D4N_F2") (pintype "passive+no_connect"))
    )
    (net (code "219") (name "unconnected-(U1H-LVDS2_D4P-PadF1)") (class "Default")
      (node (ref "U1") (pin "F1") (pinfunction "LVDS2_D4P_F1") (pintype "passive+no_connect"))
    )
    (net (code "220") (name "unconnected-(U1I-CSI_CKN-PadD4)") (class "Default")
      (node (ref "U1") (pin "D4") (pinfunction "CSI_CKN_D4") (pintype "passive+no_connect"))
    )
    (net (code "221") (name "unconnected-(U1I-CSI_CKP-PadC4)") (class "Default")
      (node (ref "U1") (pin "C4") (pinfunction "CSI_CKP_C4") (pintype "passive+no_connect"))
    )
    (net (code "222") (name "unconnected-(U1I-CSI_D0N-PadA3)") (class "Default")
      (node (ref "U1") (pin "A3") (pinfunction "CSI_D0N_A3") (pintype "passive+no_connect"))
    )
    (net (code "223") (name "unconnected-(U1I-CSI_D0P-PadB3)") (class "Default")
      (node (ref "U1") (pin "B3") (pinfunction "CSI_D0P_B3") (pintype "passive+no_connect"))
    )
    (net (code "224") (name "unconnected-(U1I-CSI_D1N-PadC5)") (class "Default")
      (node (ref "U1") (pin "C5") (pinfunction "CSI_D1N_C5") (pintype "passive+no_connect"))
    )
    (net (code "225") (name "unconnected-(U1I-CSI_D1P-PadB5)") (class "Default")
      (node (ref "U1") (pin "B5") (pinfunction "CSI_D1P_B5") (pintype "passive+no_connect"))
    )
    (net (code "226") (name "unconnected-(U1I-CSI_REXT-PadF6)") (class "Default")
      (node (ref "U1") (pin "F6") (pinfunction "CSI_REXT_F6") (pintype "passive+no_connect"))
    )
  )
)
